# Sheet1.net
KiCad netlist of a schematic drawn in Altium Designer
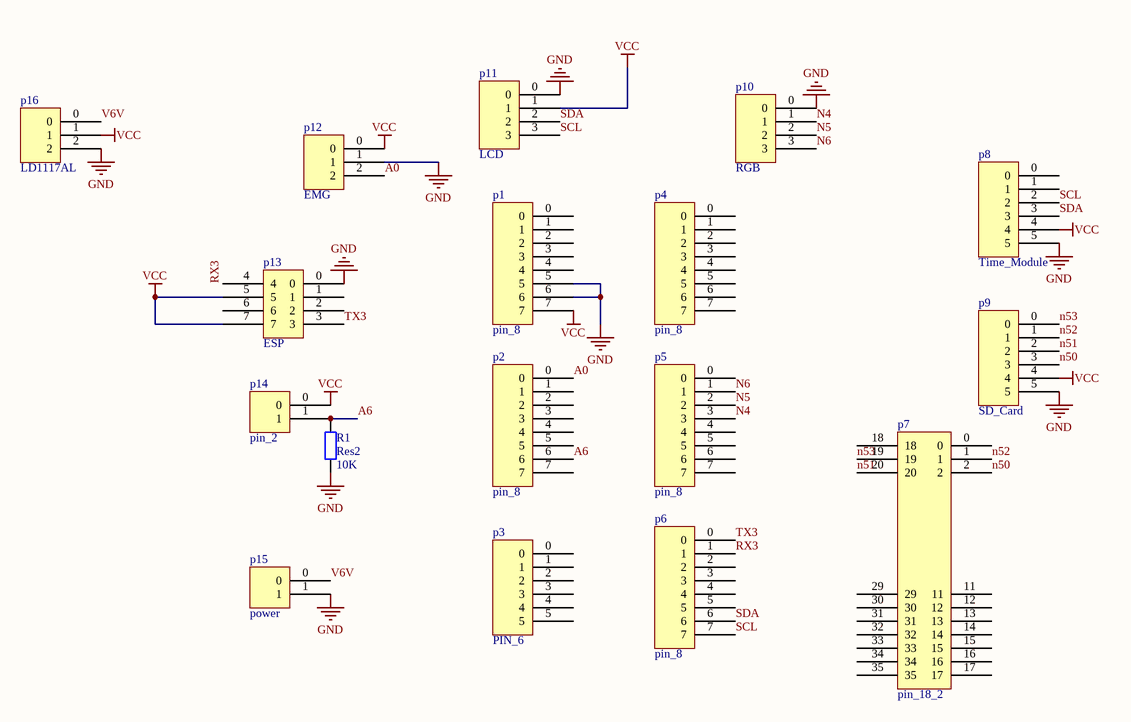
[diagram p0: Sheet1.SchDoc]

(export (version "E")
  (design (tool "Eeschema 10.0.6"))
  (components
    (comp (ref "p1")
      (value "pin_8")
      (footprint "pin_8")
      (libsource (lib "Integrated_Library") (part "pin_8"))
    )
    (comp (ref "p2")
      (value "pin_8")
      (footprint "pin_8")
      (libsource (lib "Integrated_Library") (part "pin_8"))
    )
    (comp (ref "p3")
      (value "PIN_6")
      (footprint "pin_6")
      (libsource (lib "Integrated_Library") (part "pin_6"))
    )
    (comp (ref "p4")
      (value "pin_8")
      (footprint "pin_8")
      (libsource (lib "Integrated_Library") (part "pin_8"))
    )
    (comp (ref "p5")
      (value "pin_8")
      (footprint "pin_8")
      (libsource (lib "Integrated_Library") (part "pin_8"))
    )
    (comp (ref "p6")
      (value "pin_8")
      (footprint "pin_8")
      (libsource (lib "Integrated_Library") (part "pin_8"))
    )
    (comp (ref "p7")
      (value "pin_18_2")
      (footprint "pin_18_2")
      (libsource (lib "Integrated_Library") (part "pin_18_2"))
    )
    (comp (ref "p8")
      (value "Time_Module")
      (footprint "pin_6")
      (libsource (lib "Integrated_Library") (part "pin_6"))
    )
    (comp (ref "p9")
      (value "SD_Card")
      (footprint "pin_6")
      (libsource (lib "Integrated_Library") (part "pin_6"))
    )
    (comp (ref "p10") (value "RGB") (footprint "pin_4") (libsource (lib "Integrated_Library") (part "pin_4")))
    (comp (ref "p11") (value "LCD") (footprint "pin_4") (libsource (lib "Integrated_Library") (part "pin_4")))
    (comp (ref "p12") (value "EMG") (footprint "PIN_3") (libsource (lib "Integrated_Library") (part "pin_3")))
    (comp (ref "p13")
      (value "ESP")
      (footprint "pin_4_2")
      (libsource (lib "Integrated_Library") (part "pin_4_2"))
    )
    (comp (ref "p14")
      (value "pin_2")
      (footprint "PIN_2")
      (libsource (lib "Integrated_Library") (part "pin_2"))
    )
    (comp (ref "p15")
      (value "power")
      (footprint "PIN_2")
      (libsource (lib "Integrated_Library") (part "pin_2"))
    )
    (comp (ref "p16")
      (value "LD1117AL")
      (footprint "PIN_3")
      (libsource (lib "Integrated_Library") (part "pin_3"))
    )
    (comp (ref "R1")
      (value "Res2")
      (footprint "AXIAL-0.4")
      (description "Resistor")
      (fields (field (name "ALTIUM_VALUE") "10K") (field (name "PUBLISHER") "Altium Limited"))
      (libsource (lib "Miscellaneous Devices") (part "Res2"))
    )
  )
  (nets
    (net (code "1") (name "/A0") (class "Default")
      (node (ref "p12") (pin "2") (pinfunction "2_2") (pintype "passive"))
      (node (ref "p2") (pin "0") (pinfunction "0_0") (pintype "passive"))
    )
    (net (code "2") (name "/A6") (class "Default")
      (node (ref "R1") (pin "2") (pinfunction "2_2") (pintype "passive"))
      (node (ref "p14") (pin "1") (pinfunction "1_1") (pintype "passive"))
      (node (ref "p2") (pin "6") (pinfunction "6_6") (pintype "passive"))
    )
    (net (code "3") (name "/N4") (class "Default")
      (node (ref "p10") (pin "1") (pinfunction "1_1") (pintype "passive"))
      (node (ref "p5") (pin "3") (pinfunction "3_3") (pintype "passive"))
    )
    (net (code "4") (name "/N5") (class "Default")
      (node (ref "p10") (pin "2") (pinfunction "2_2") (pintype "passive"))
      (node (ref "p5") (pin "2") (pinfunction "2_2") (pintype "passive"))
    )
    (net (code "5") (name "/N6") (class "Default")
      (node (ref "p10") (pin "3") (pinfunction "3_3") (pintype "passive"))
      (node (ref "p5") (pin "1") (pinfunction "1_1") (pintype "passive"))
    )
    (net (code "6") (name "/RX3") (class "Default")
      (node (ref "p13") (pin "4") (pinfunction "4_4") (pintype "passive"))
      (node (ref "p6") (pin "1") (pinfunction "1_1") (pintype "passive"))
    )
    (net (code "7") (name "/SCL") (class "Default")
      (node (ref "p11") (pin "3") (pinfunction "3_3") (pintype "passive"))
      (node (ref "p6") (pin "7") (pinfunction "7_7") (pintype "passive"))
      (node (ref "p8") (pin "2") (pinfunction "2_2") (pintype "passive"))
    )
    (net (code "8") (name "/SDA") (class "Default")
      (node (ref "p11") (pin "2") (pinfunction "2_2") (pintype "passive"))
      (node (ref "p6") (pin "6") (pinfunction "6_6") (pintype "passive"))
      (node (ref "p8") (pin "3") (pinfunction "3_3") (pintype "passive"))
    )
    (net (code "9") (name "/TX3") (class "Default")
      (node (ref "p13") (pin "3") (pinfunction "3_3") (pintype "passive"))
      (node (ref "p6") (pin "0") (pinfunction "0_0") (pintype "passive"))
    )
    (net (code "10") (name "/V6V") (class "Default")
      (node (ref "p15") (pin "0") (pinfunction "0_0") (pintype "passive"))
      (node (ref "p16") (pin "0") (pinfunction "0_0") (pintype "passive"))
    )
    (net (code "11") (name "/n50") (class "Default")
      (node (ref "p7") (pin "2") (pinfunction "2_2") (pintype "passive"))
      (node (ref "p9") (pin "3") (pinfunction "3_3") (pintype "passive"))
    )
    (net (code "12") (name "/n51") (class "Default")
      (node (ref "p7") (pin "20") (pinfunction "20_20") (pintype "passive"))
      (node (ref "p9") (pin "2") (pinfunction "2_2") (pintype "passive"))
    )
    (net (code "13") (name "/n52") (class "Default")
      (node (ref "p7") (pin "1") (pinfunction "1_1") (pintype "passive"))
      (node (ref "p9") (pin "1") (pinfunction "1_1") (pintype "passive"))
    )
    (net (code "14") (name "/n53") (class "Default")
      (node (ref "p7") (pin "19") (pinfunction "19_19") (pintype "passive"))
      (node (ref "p9") (pin "0") (pinfunction "0_0") (pintype "passive"))
    )
    (net (code "15") (name "GND") (class "Default")
      (node (ref "R1") (pin "1") (pinfunction "1_1") (pintype "passive"))
      (node (ref "p1") (pin "5") (pinfunction "5_5") (pintype "passive"))
      (node (ref "p1") (pin "6") (pinfunction "6_6") (pintype "passive"))
      (node (ref "p10") (pin "0") (pinfunction "0_0") (pintype "passive"))
      (node (ref "p11") (pin "0") (pinfunction "0_0") (pintype "passive"))
      (node (ref "p12") (pin "1") (pinfunction "1_1") (pintype "passive"))
      (node (ref "p13") (pin "0") (pinfunction "0_0") (pintype "passive"))
      (node (ref "p15") (pin "1") (pinfunction "1_1") (pintype "passive"))
      (node (ref "p16") (pin "2") (pinfunction "2_2") (pintype "passive"))
      (node (ref "p8") (pin "5") (pinfunction "5_5") (pintype "passive"))
      (node (ref "p9") (pin "5") (pinfunction "5_5") (pintype "passive"))
    )
    (net (code "16") (name "VCC") (class "Default")
      (node (ref "p1") (pin "7") (pinfunction "7_7") (pintype "passive"))
      (node (ref "p11") (pin "1") (pinfunction "1_1") (pintype "passive"))
      (node (ref "p12") (pin "0") (pinfunction "0_0") (pintype "passive"))
      (node (ref "p13") (pin "5") (pinfunction "5_5") (pintype "passive"))
      (node (ref "p13") (pin "7") (pinfunction "7_7") (pintype "passive"))
      (node (ref "p14") (pin "0") (pinfunction "0_0") (pintype "passive"))
      (node (ref "p16") (pin "1") (pinfunction "1_1") (pintype "passive"))
      (node (ref "p8") (pin "4") (pinfunction "4_4") (pintype "passive"))
      (node (ref "p9") (pin "4") (pinfunction "4_4") (pintype "passive"))
    )
    (net (code "17") (name "unconnected-(p1-Pad0)") (class "Default")
      (node (ref "p1") (pin "0") (pinfunction "0_0") (pintype "passive"))
    )
    (net (code "18") (name "unconnected-(p1-Pad1)") (class "Default")
      (node (ref "p1") (pin "1") (pinfunction "1_1") (pintype "passive"))
    )
    (net (code "19") (name "unconnected-(p1-Pad2)") (class "Default")
      (node (ref "p1") (pin "2") (pinfunction "2_2") (pintype "passive"))
    )
    (net (code "20") (name "unconnected-(p1-Pad3)") (class "Default")
      (node (ref "p1") (pin "3") (pinfunction "3_3") (pintype "passive"))
    )
    (net (code "21") (name "unconnected-(p1-Pad4)") (class "Default")
      (node (ref "p1") (pin "4") (pinfunction "4_4") (pintype "passive"))
    )
    (net (code "22") (name "unconnected-(p2-Pad1)") (class "Default")
      (node (ref "p2") (pin "1") (pinfunction "1_1") (pintype "passive"))
    )
    (net (code "23") (name "unconnected-(p2-Pad2)") (class "Default")
      (node (ref "p2") (pin "2") (pinfunction "2_2") (pintype "passive"))
    )
    (net (code "24") (name "unconnected-(p2-Pad3)") (class "Default")
      (node (ref "p2") (pin "3") (pinfunction "3_3") (pintype "passive"))
    )
    (net (code "25") (name "unconnected-(p2-Pad4)") (class "Default")
      (node (ref "p2") (pin "4") (pinfunction "4_4") (pintype "passive"))
    )
    (net (code "26") (name "unconnected-(p2-Pad5)") (class "Default")
      (node (ref "p2") (pin "5") (pinfunction "5_5") (pintype "passive"))
    )
    (net (code "27") (name "unconnected-(p2-Pad7)") (class "Default")
      (node (ref "p2") (pin "7") (pinfunction "7_7") (pintype "passive"))
    )
    (net (code "28") (name "unconnected-(p3-Pad0)") (class "Default")
      (node (ref "p3") (pin "0") (pinfunction "0_0") (pintype "passive"))
    )
    (net (code "29") (name "unconnected-(p3-Pad1)") (class "Default")
      (node (ref "p3") (pin "1") (pinfunction "1_1") (pintype "passive"))
    )
    (net (code "30") (name "unconnected-(p3-Pad2)") (class "Default")
      (node (ref "p3") (pin "2") (pinfunction "2_2") (pintype "passive"))
    )
    (net (code "31") (name "unconnected-(p3-Pad3)") (class "Default")
      (node (ref "p3") (pin "3") (pinfunction "3_3") (pintype "passive"))
    )
    (net (code "32") (name "unconnected-(p3-Pad4)") (class "Default")
      (node (ref "p3") (pin "4") (pinfunction "4_4") (pintype "passive"))
    )
    (net (code "33") (name "unconnected-(p3-Pad5)") (class "Default")
      (node (ref "p3") (pin "5") (pinfunction "5_5") (pintype "passive"))
    )
    (net (code "34") (name "unconnected-(p4-Pad0)") (class "Default")
      (node (ref "p4") (pin "0") (pinfunction "0_0") (pintype "passive"))
    )
    (net (code "35") (name "unconnected-(p4-Pad1)") (class "Default")
      (node (ref "p4") (pin "1") (pinfunction "1_1") (pintype "passive"))
    )
    (net (code "36") (name "unconnected-(p4-Pad2)") (class "Default")
      (node (ref "p4") (pin "2") (pinfunction "2_2") (pintype "passive"))
    )
    (net (code "37") (name "unconnected-(p4-Pad3)") (class "Default")
      (node (ref "p4") (pin "3") (pinfunction "3_3") (pintype "passive"))
    )
    (net (code "38") (name "unconnected-(p4-Pad4)") (class "Default")
      (node (ref "p4") (pin "4") (pinfunction "4_4") (pintype "passive"))
    )
    (net (code "39") (name "unconnected-(p4-Pad5)") (class "Default")
      (node (ref "p4") (pin "5") (pinfunction "5_5") (pintype "passive"))
    )
    (net (code "40") (name "unconnected-(p4-Pad6)") (class "Default")
      (node (ref "p4") (pin "6") (pinfunction "6_6") (pintype "passive"))
    )
    (net (code "41") (name "unconnected-(p4-Pad7)") (class "Default")
      (node (ref "p4") (pin "7") (pinfunction "7_7") (pintype "passive"))
    )
    (net (code "42") (name "unconnected-(p5-Pad0)") (class "Default")
      (node (ref "p5") (pin "0") (pinfunction "0_0") (pintype "passive"))
    )
    (net (code "43") (name "unconnected-(p5-Pad4)") (class "Default")
      (node (ref "p5") (pin "4") (pinfunction "4_4") (pintype "passive"))
    )
    (net (code "44") (name "unconnected-(p5-Pad5)") (class "Default")
      (node (ref "p5") (pin "5") (pinfunction "5_5") (pintype "passive"))
    )
    (net (code "45") (name "unconnected-(p5-Pad6)") (class "Default")
      (node (ref "p5") (pin "6") (pinfunction "6_6") (pintype "passive"))
    )
    (net (code "46") (name "unconnected-(p5-Pad7)") (class "Default")
      (node (ref "p5") (pin "7") (pinfunction "7_7") (pintype "passive"))
    )
    (net (code "47") (name "unconnected-(p6-Pad2)") (class "Default")
      (node (ref "p6") (pin "2") (pinfunction "2_2") (pintype "passive"))
    )
    (net (code "48") (name "unconnected-(p6-Pad3)") (class "Default")
      (node (ref "p6") (pin "3") (pinfunction "3_3") (pintype "passive"))
    )
    (net (code "49") (name "unconnected-(p6-Pad4)") (class "Default")
      (node (ref "p6") (pin "4") (pinfunction "4_4") (pintype "passive"))
    )
    (net (code "50") (name "unconnected-(p6-Pad5)") (class "Default")
      (node (ref "p6") (pin "5") (pinfunction "5_5") (pintype "passive"))
    )
    (net (code "51") (name "unconnected-(p7-Pad0)") (class "Default")
      (node (ref "p7") (pin "0") (pinfunction "0_0") (pintype "passive"))
    )
    (net (code "52") (name "unconnected-(p7-Pad11)") (class "Default")
      (node (ref "p7") (pin "11") (pinfunction "11_11") (pintype "passive"))
    )
    (net (code "53") (name "unconnected-(p7-Pad12)") (class "Default")
      (node (ref "p7") (pin "12") (pinfunction "12_12") (pintype "passive"))
    )
    (net (code "54") (name "unconnected-(p7-Pad13)") (class "Default")
      (node (ref "p7") (pin "13") (pinfunction "13_13") (pintype "passive"))
    )
    (net (code "55") (name "unconnected-(p7-Pad14)") (class "Default")
      (node (ref "p7") (pin "14") (pinfunction "14_14") (pintype "passive"))
    )
    (net (code "56") (name "unconnected-(p7-Pad15)") (class "Default")
      (node (ref "p7") (pin "15") (pinfunction "15_15") (pintype "passive"))
    )
    (net (code "57") (name "unconnected-(p7-Pad16)") (class "Default")
      (node (ref "p7") (pin "16") (pinfunction "16_16") (pintype "passive"))
    )
    (net (code "58") (name "unconnected-(p7-Pad17)") (class "Default")
      (node (ref "p7") (pin "17") (pinfunction "17_17") (pintype "passive"))
    )
    (net (code "59") (name "unconnected-(p7-Pad18)") (class "Default")
      (node (ref "p7") (pin "18") (pinfunction "18_18") (pintype "passive"))
    )
    (net (code "60") (name "unconnected-(p7-Pad29)") (class "Default")
      (node (ref "p7") (pin "29") (pinfunction "29_29") (pintype "passive"))
    )
    (net (code "61") (name "unconnected-(p7-Pad30)") (class "Default")
      (node (ref "p7") (pin "30") (pinfunction "30_30") (pintype "passive"))
    )
    (net (code "62") (name "unconnected-(p7-Pad31)") (class "Default")
      (node (ref "p7") (pin "31") (pinfunction "31_31") (pintype "passive"))
    )
    (net (code "63") (name "unconnected-(p7-Pad32)") (class "Default")
      (node (ref "p7") (pin "32") (pinfunction "32_32") (pintype "passive"))
    )
    (net (code "64") (name "unconnected-(p7-Pad33)") (class "Default")
      (node (ref "p7") (pin "33") (pinfunction "33_33") (pintype "passive"))
    )
    (net (code "65") (name "unconnected-(p7-Pad34)") (class "Default")
      (node (ref "p7") (pin "34") (pinfunction "34_34") (pintype "passive"))
    )
    (net (code "66") (name "unconnected-(p7-Pad35)") (class "Default")
      (node (ref "p7") (pin "35") (pinfunction "35_35") (pintype "passive"))
    )
    (net (code "67") (name "unconnected-(p8-Pad0)") (class "Default")
      (node (ref "p8") (pin "0") (pinfunction "0_0") (pintype "passive"))
    )
    (net (code "68") (name "unconnected-(p8-Pad1)") (class "Default")
      (node (ref "p8") (pin "1") (pinfunction "1_1") (pintype "passive"))
    )
    (net (code "69") (name "unconnected-(p13-Pad1)") (class "Default")
      (node (ref "p13") (pin "1") (pinfunction "1_1") (pintype "passive"))
    )
    (net (code "70") (name "unconnected-(p13-Pad2)") (class "Default")
      (node (ref "p13") (pin "2") (pinfunction "2_2") (pintype "passive"))
    )
    (net (code "71") (name "unconnected-(p13-Pad6)") (class "Default")
      (node (ref "p13") (pin "6") (pinfunction "6_6") (pintype "passive"))
    )
  )
)
